# power_supply.net
KiCad netlist of a schematic drawn in EAGLE
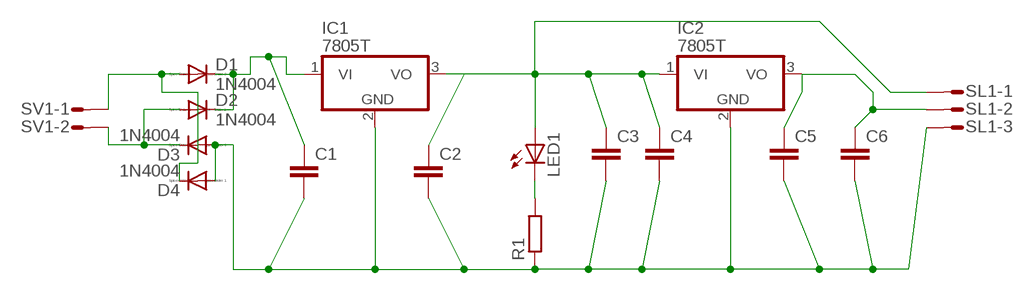
[diagram p0: schematic, sheet 1]

(export (version "E")
  (design (tool "Eeschema 10.0.6"))
  (components
    (comp (ref "C1")
      (value "C5/5.5")
      (footprint "eagle-import:C5B5.5")
      (libsource (lib "eagle-import") (part "C5/5.5"))
    )
    (comp (ref "C2")
      (value "C5/5.5")
      (footprint "eagle-import:C5B5.5")
      (libsource (lib "eagle-import") (part "C5/5.5"))
    )
    (comp (ref "C3")
      (value "C5/5.5")
      (footprint "eagle-import:C5B5.5")
      (libsource (lib "eagle-import") (part "C5/5.5"))
    )
    (comp (ref "C4")
      (value "C5/5.5")
      (footprint "eagle-import:C5B5.5")
      (libsource (lib "eagle-import") (part "C5/5.5"))
    )
    (comp (ref "C5")
      (value "C5/5.5")
      (footprint "eagle-import:C5B5.5")
      (libsource (lib "eagle-import") (part "C5/5.5"))
    )
    (comp (ref "C6")
      (value "C5/5.5")
      (footprint "eagle-import:C5B5.5")
      (libsource (lib "eagle-import") (part "C5/5.5"))
    )
    (comp (ref "D1")
      (value "1N4004")
      (footprint "eagle-import:DO41-10")
      (libsource (lib "eagle-import") (part "1N4004"))
    )
    (comp (ref "D2")
      (value "1N4004")
      (footprint "eagle-import:DO41-10")
      (libsource (lib "eagle-import") (part "1N4004"))
    )
    (comp (ref "D3")
      (value "1N4004")
      (footprint "eagle-import:DO41-10")
      (libsource (lib "eagle-import") (part "1N4004"))
    )
    (comp (ref "D4")
      (value "1N4004")
      (footprint "eagle-import:DO41-10")
      (libsource (lib "eagle-import") (part "1N4004"))
    )
    (comp (ref "IC1")
      (value "7805T")
      (footprint "eagle-import:TO220H")
      (libsource (lib "eagle-import") (part "78T05"))
    )
    (comp (ref "IC2")
      (value "7805T")
      (footprint "eagle-import:TO220H")
      (libsource (lib "eagle-import") (part "78T05"))
    )
    (comp (ref "LED1")
      (value "LED5MM")
      (footprint "eagle-import:LED5MM")
      (libsource (lib "eagle-import") (part "LED5MM"))
    )
    (comp (ref "R1")
      (value "R-EU_0207/7")
      (footprint "eagle-import:0207_7")
      (libsource (lib "eagle-import") (part "R-EU_0207/7"))
    )
    (comp (ref "SL1")
      (value "M03S")
      (footprint "eagle-import:03P")
      (libsource (lib "eagle-import") (part "M03S"))
    )
    (comp (ref "SV1")
      (value "L02P")
      (footprint "eagle-import:L02P")
      (libsource (lib "eagle-import") (part "L02P"))
    )
  )
  (nets
    (net (code "1") (name "Net-(IC1-GND)") (class "Default")
      (node (ref "C1") (pin "2") (pinfunction "2_2") (pintype "passive"))
      (node (ref "C2") (pin "2") (pinfunction "2_2") (pintype "passive"))
      (node (ref "C3") (pin "2") (pinfunction "2_2") (pintype "passive"))
      (node (ref "C4") (pin "2") (pinfunction "2_2") (pintype "passive"))
      (node (ref "C5") (pin "2") (pinfunction "2_2") (pintype "passive"))
      (node (ref "C6") (pin "2") (pinfunction "2_2") (pintype "passive"))
      (node (ref "D3") (pin "A") (pinfunction "A_A") (pintype "passive"))
      (node (ref "D4") (pin "A") (pinfunction "A_A") (pintype "passive"))
      (node (ref "IC1") (pin "2") (pinfunction "GND_2") (pintype "passive"))
      (node (ref "IC2") (pin "2") (pinfunction "GND_2") (pintype "passive"))
      (node (ref "R1") (pin "1") (pinfunction "1_1") (pintype "passive"))
      (node (ref "SL1") (pin "3") (pinfunction "S_3") (pintype "passive"))
    )
    (net (code "2") (name "Net-(IC1-VI)") (class "Default")
      (node (ref "C1") (pin "1") (pinfunction "1_1") (pintype "passive"))
      (node (ref "D1") (pin "C") (pinfunction "C_C") (pintype "passive"))
      (node (ref "D2") (pin "C") (pinfunction "C_C") (pintype "passive"))
      (node (ref "IC1") (pin "1") (pinfunction "VI_1") (pintype "input"))
    )
    (net (code "3") (name "Net-(IC1-VO)") (class "Default")
      (node (ref "C2") (pin "1") (pinfunction "1_1") (pintype "passive"))
      (node (ref "C3") (pin "1") (pinfunction "1_1") (pintype "passive"))
      (node (ref "C4") (pin "1") (pinfunction "1_1") (pintype "passive"))
      (node (ref "IC1") (pin "3") (pinfunction "VO_3") (pintype "passive"))
      (node (ref "IC2") (pin "1") (pinfunction "VI_1") (pintype "input"))
      (node (ref "LED1") (pin "A") (pinfunction "A_A") (pintype "passive"))
      (node (ref "SL1") (pin "1") (pinfunction "S_1") (pintype "passive"))
    )
    (net (code "4") (name "Net-(IC2-VO)") (class "Default")
      (node (ref "C5") (pin "1") (pinfunction "1_1") (pintype "passive"))
      (node (ref "C6") (pin "1") (pinfunction "1_1") (pintype "passive"))
      (node (ref "IC2") (pin "3") (pinfunction "VO_3") (pintype "passive"))
      (node (ref "SL1") (pin "2") (pinfunction "S_2") (pintype "passive"))
    )
    (net (code "5") (name "Net-(LED1-C)") (class "Default")
      (node (ref "LED1") (pin "K") (pinfunction "C_K") (pintype "passive"))
      (node (ref "R1") (pin "2") (pinfunction "2_2") (pintype "passive"))
    )
    (net (code "6") (name "Net-(SV1A-S)") (class "Default")
      (node (ref "D1") (pin "A") (pinfunction "A_A") (pintype "passive"))
      (node (ref "D4") (pin "C") (pinfunction "C_C") (pintype "passive"))
      (node (ref "SV1") (pin "1") (pinfunction "S_1") (pintype "passive"))
    )
    (net (code "7") (name "Net-(SV1B-S)") (class "Default")
      (node (ref "D2") (pin "A") (pinfunction "A_A") (pintype "passive"))
      (node (ref "D3") (pin "C") (pinfunction "C_C") (pintype "passive"))
      (node (ref "SV1") (pin "2") (pinfunction "S_2") (pintype "passive"))
    )
  )
)
